# nes2msx.net
KiCad netlist of a schematic drawn in EAGLE
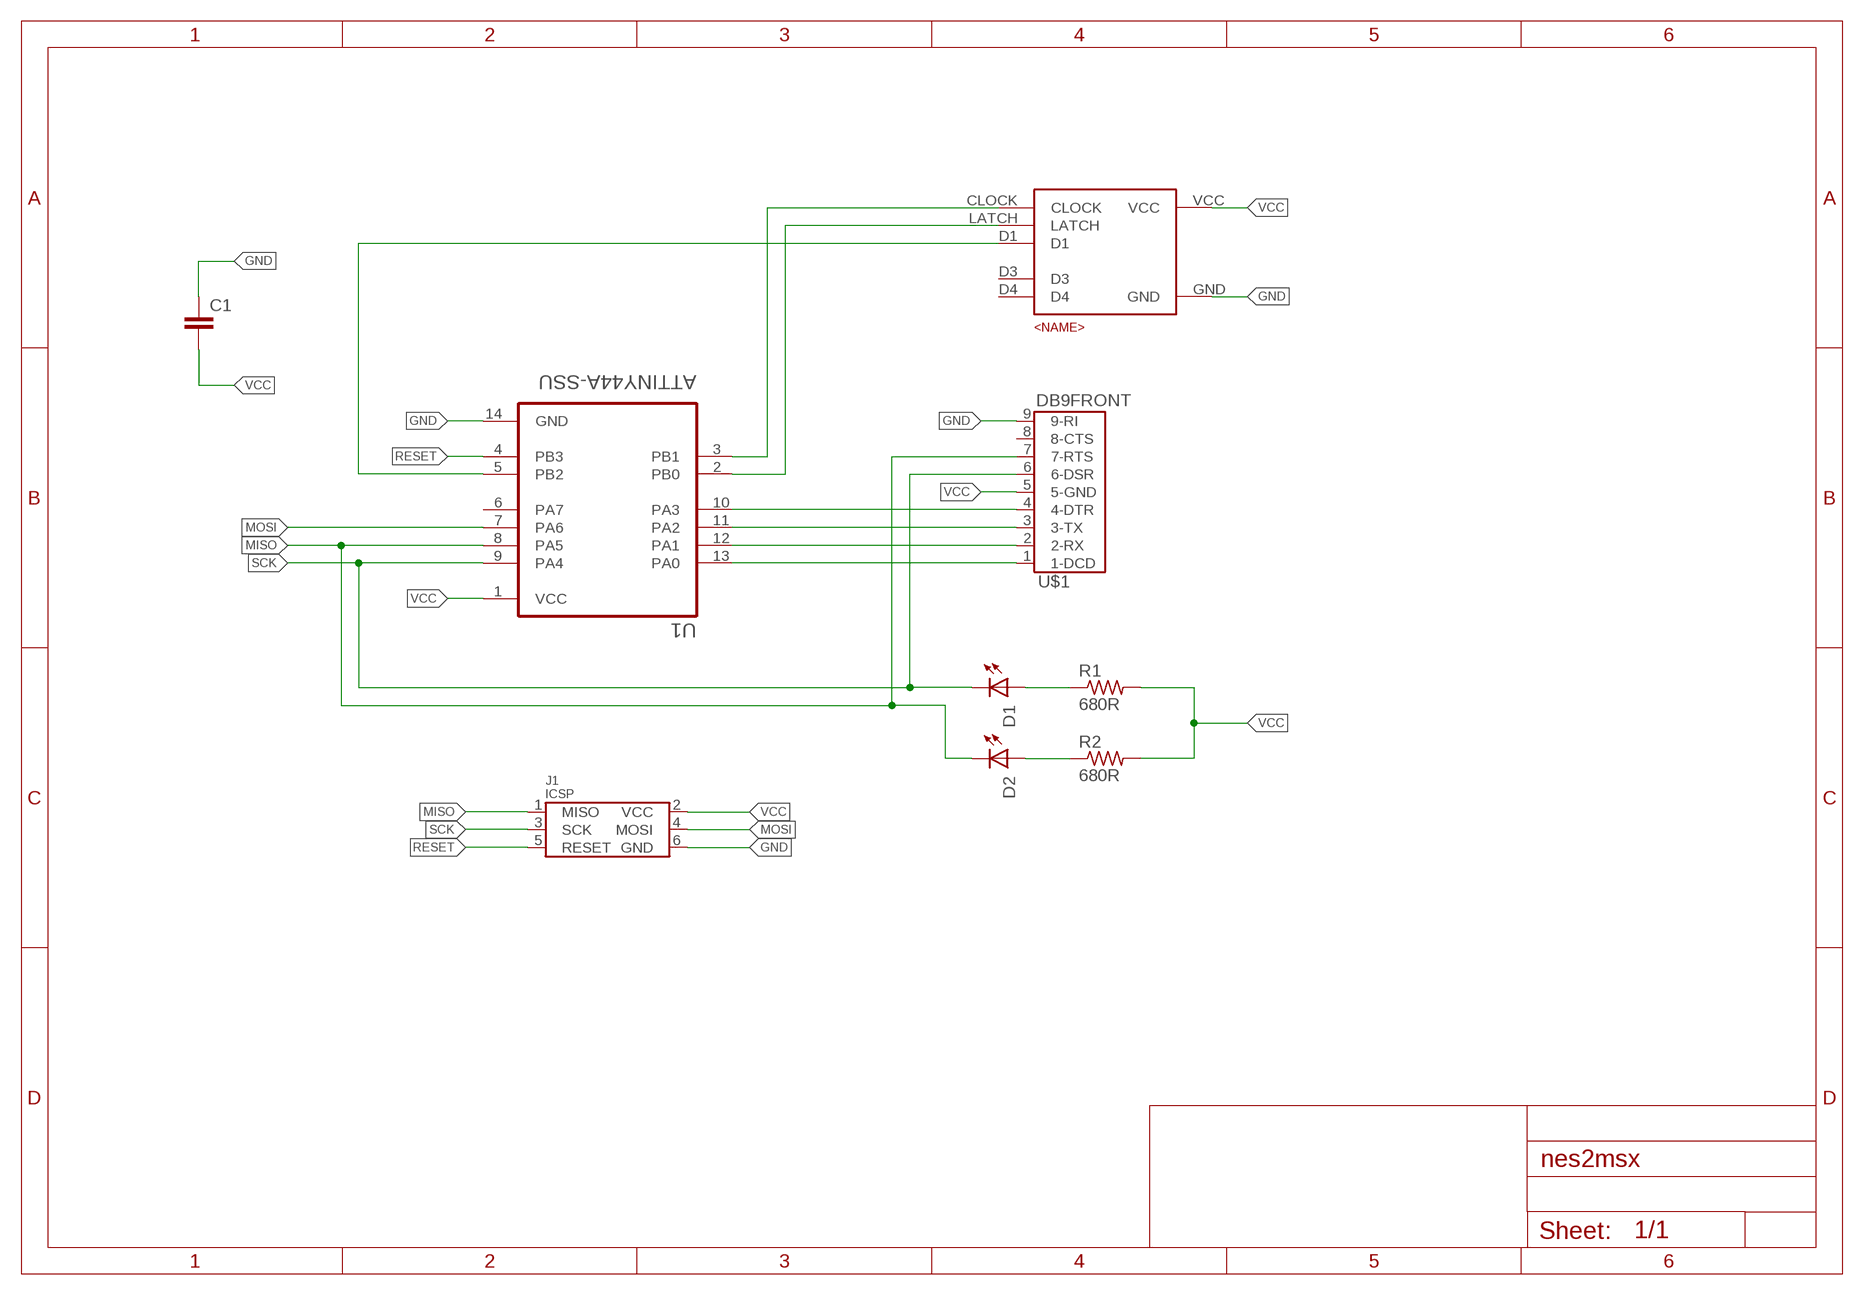
[diagram p0: schematic, sheet 1]

(export (version "E")
  (design (tool "Eeschema 10.0.6"))
  (components
    (comp (ref "C1")
      (value "C-EUC0805")
      (footprint "eagle-import:C0805")
      (libsource (lib "eagle-import") (part "C-EUC0805"))
    )
    (comp (ref "D1")
      (value "LED-0805")
      (footprint "eagle-import:0805-LED")
      (libsource (lib "eagle-import") (part "LED-0805"))
    )
    (comp (ref "D2")
      (value "LED-0805")
      (footprint "eagle-import:0805-LED")
      (libsource (lib "eagle-import") (part "LED-0805"))
    )
    (comp (ref "J1")
      (value "ICSP")
      (footprint "eagle-import:M03X2")
      (libsource (lib "eagle-import") (part "ICSP"))
    )
    (comp (ref "R1")
      (value "680R")
      (footprint "eagle-import:R0805")
      (libsource (lib "eagle-import") (part "R-US_R0805"))
    )
    (comp (ref "R2")
      (value "680R")
      (footprint "eagle-import:R0805")
      (libsource (lib "eagle-import") (part "R-US_R0805"))
    )
    (comp (ref "U$1")
      (value "DB9FRONT")
      (footprint "eagle-import:DB9_FRONT")
      (libsource (lib "eagle-import") (part "DB9FRONT"))
    )
    (comp (ref "U$3")
      (value "NES_CONTROLLERL")
      (footprint "eagle-import:NES_CONTROLLER")
      (libsource (lib "eagle-import") (part "NES_CONTROLLERL"))
    )
    (comp (ref "U1")
      (value "ATTINY44A-SSU")
      (footprint "eagle-import:SOIC127P600X175-14N")
      (fields (field (name "MF") "Microchip"))
      (libsource (lib "eagle-import") (part "ATTINY44A-SSU"))
    )
  )
  (nets
    (net (code "1") (name "GND") (class "Default")
      (node (ref "C1") (pin "1") (pinfunction "1_1") (pintype "passive"))
      (node (ref "J1") (pin "6") (pinfunction "GND_6") (pintype "bidirectional"))
      (node (ref "U$1") (pin "9") (pinfunction "9-RI_9") (pintype "bidirectional"))
      (node (ref "U$3") (pin "GND") (pinfunction "GND_GND") (pintype "bidirectional"))
      (node (ref "U1") (pin "14") (pinfunction "GND_14") (pintype "power_in"))
    )
    (net (code "2") (name "MISO") (class "Default")
      (node (ref "D2") (pin "C") (pinfunction "C_C") (pintype "passive"))
      (node (ref "J1") (pin "1") (pinfunction "MISO_1") (pintype "bidirectional"))
      (node (ref "U$1") (pin "7") (pinfunction "7-RTS_7") (pintype "bidirectional"))
      (node (ref "U1") (pin "8") (pinfunction "PA5_8") (pintype "bidirectional"))
    )
    (net (code "3") (name "MOSI") (class "Default")
      (node (ref "J1") (pin "4") (pinfunction "MOSI_4") (pintype "bidirectional"))
      (node (ref "U1") (pin "7") (pinfunction "PA6_7") (pintype "bidirectional"))
    )
    (net (code "4") (name "Net-(D1-PadA)") (class "Default")
      (node (ref "D1") (pin "A") (pinfunction "A_A") (pintype "passive"))
      (node (ref "R1") (pin "1") (pinfunction "1_1") (pintype "passive"))
    )
    (net (code "5") (name "Net-(D2-PadA)") (class "Default")
      (node (ref "D2") (pin "A") (pinfunction "A_A") (pintype "passive"))
      (node (ref "R2") (pin "1") (pinfunction "1_1") (pintype "passive"))
    )
    (net (code "6") (name "Net-(U$1-1-DCD)") (class "Default")
      (node (ref "U$1") (pin "1") (pinfunction "1-DCD_1") (pintype "bidirectional"))
      (node (ref "U1") (pin "13") (pinfunction "PA0_13") (pintype "bidirectional"))
    )
    (net (code "7") (name "Net-(U$1-2-RX)") (class "Default")
      (node (ref "U$1") (pin "2") (pinfunction "2-RX_2") (pintype "bidirectional"))
      (node (ref "U1") (pin "12") (pinfunction "PA1_12") (pintype "bidirectional"))
    )
    (net (code "8") (name "Net-(U$1-3-TX)") (class "Default")
      (node (ref "U$1") (pin "3") (pinfunction "3-TX_3") (pintype "bidirectional"))
      (node (ref "U1") (pin "11") (pinfunction "PA2_11") (pintype "bidirectional"))
    )
    (net (code "9") (name "Net-(U$1-4-DTR)") (class "Default")
      (node (ref "U$1") (pin "4") (pinfunction "4-DTR_4") (pintype "bidirectional"))
      (node (ref "U1") (pin "10") (pinfunction "PA3_10") (pintype "bidirectional"))
    )
    (net (code "10") (name "Net-(U1-PB0)") (class "Default")
      (node (ref "U$3") (pin "LATCH") (pinfunction "LATCH_LATCH") (pintype "bidirectional"))
      (node (ref "U1") (pin "2") (pinfunction "PB0_2") (pintype "bidirectional"))
    )
    (net (code "11") (name "Net-(U1-PB1)") (class "Default")
      (node (ref "U$3") (pin "CLOCK") (pinfunction "CLOCK_CLOCK") (pintype "bidirectional"))
      (node (ref "U1") (pin "3") (pinfunction "PB1_3") (pintype "bidirectional"))
    )
    (net (code "12") (name "Net-(U1-PB2)") (class "Default")
      (node (ref "U$3") (pin "D1") (pinfunction "D1_D1") (pintype "bidirectional"))
      (node (ref "U1") (pin "5") (pinfunction "PB2_5") (pintype "bidirectional"))
    )
    (net (code "13") (name "RESET") (class "Default")
      (node (ref "J1") (pin "5") (pinfunction "RESET_5") (pintype "bidirectional"))
      (node (ref "U1") (pin "4") (pinfunction "PB3_4") (pintype "bidirectional"))
    )
    (net (code "14") (name "SCK") (class "Default")
      (node (ref "D1") (pin "C") (pinfunction "C_C") (pintype "passive"))
      (node (ref "J1") (pin "3") (pinfunction "SCK_3") (pintype "bidirectional"))
      (node (ref "U$1") (pin "6") (pinfunction "6-DSR_6") (pintype "bidirectional"))
      (node (ref "U1") (pin "9") (pinfunction "PA4_9") (pintype "bidirectional"))
    )
    (net (code "15") (name "VCC") (class "Default")
      (node (ref "C1") (pin "2") (pinfunction "2_2") (pintype "passive"))
      (node (ref "J1") (pin "2") (pinfunction "VCC_2") (pintype "bidirectional"))
      (node (ref "R1") (pin "2") (pinfunction "2_2") (pintype "passive"))
      (node (ref "R2") (pin "2") (pinfunction "2_2") (pintype "passive"))
      (node (ref "U$1") (pin "5") (pinfunction "5-GND_5") (pintype "bidirectional"))
      (node (ref "U$3") (pin "VCC") (pinfunction "VCC_VCC") (pintype "bidirectional"))
      (node (ref "U1") (pin "1") (pinfunction "VCC_1") (pintype "power_in"))
    )
    (net (code "16") (name "unconnected-(U$1-8-CTS-Pad8)") (class "Default")
      (node (ref "U$1") (pin "8") (pinfunction "8-CTS_8") (pintype "bidirectional"))
    )
    (net (code "17") (name "unconnected-(U$3-PadD3)") (class "Default")
      (node (ref "U$3") (pin "D3") (pinfunction "D3_D3") (pintype "bidirectional"))
    )
    (net (code "18") (name "unconnected-(U$3-PadD4)") (class "Default")
      (node (ref "U$3") (pin "D4") (pinfunction "D4_D4") (pintype "bidirectional"))
    )
    (net (code "19") (name "unconnected-(U1-PA7-Pad6)") (class "Default")
      (node (ref "U1") (pin "6") (pinfunction "PA7_6") (pintype "bidirectional"))
    )
  )
)
